# 40-auxiliary-octopus-cable.net
KiCad netlist of a schematic drawn in EAGLE
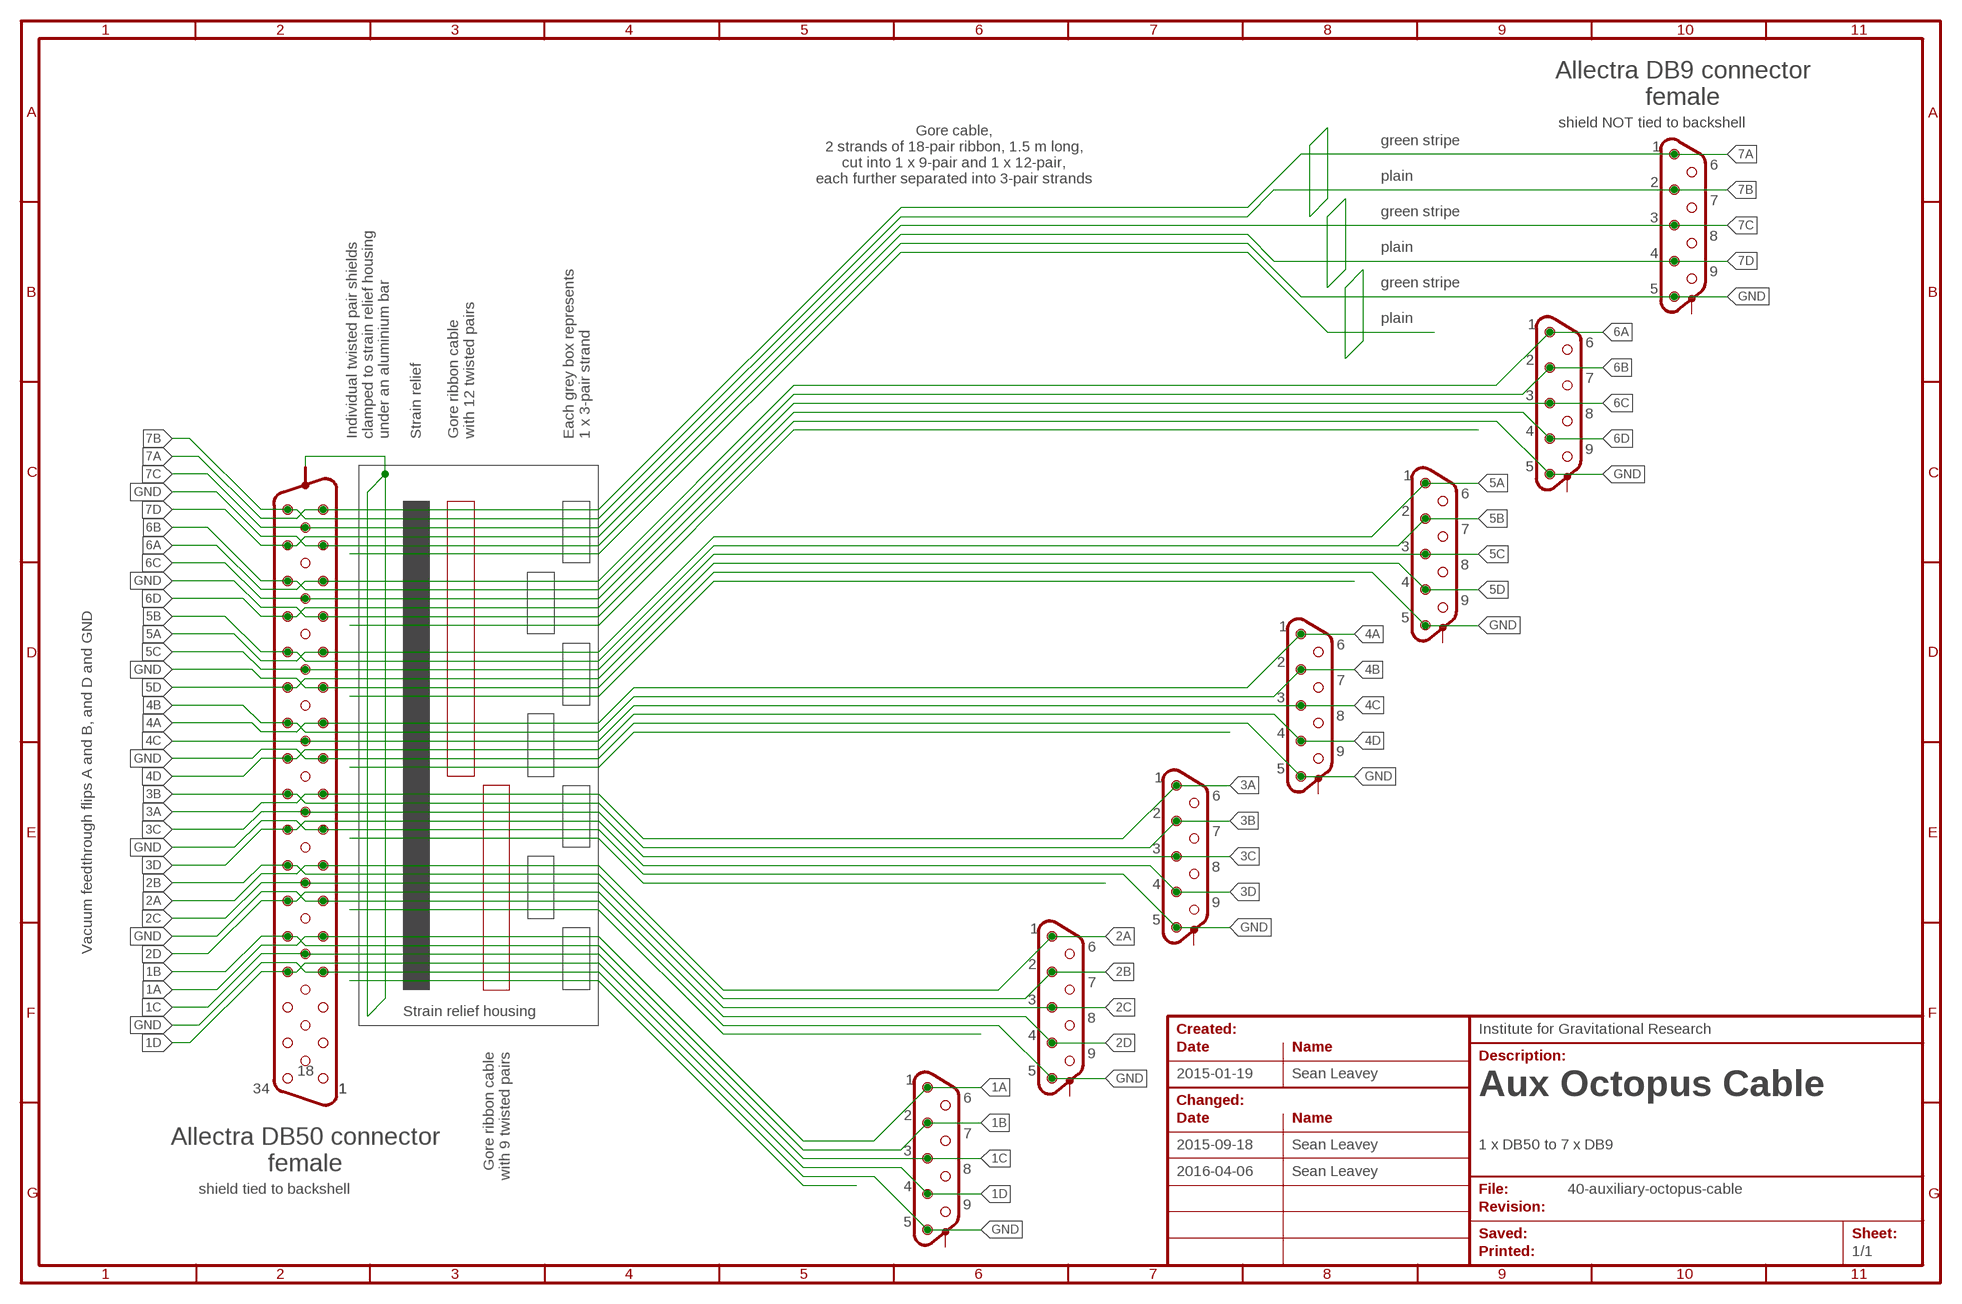
[diagram p0: schematic, sheet 1]

(export (version "E")
  (design (tool "Eeschema 10.0.6"))
  (components
    (comp (ref "U$7")
      (value "XDSUB50-SHIELD")
      (footprint "eagle-import:DUMMY50")
      (libsource (lib "eagle-import") (part "XDSUB50-SHIELD"))
    )
    (comp (ref "X43")
      (value "XDSUB9-SHIELD")
      (footprint "eagle-import:DUMMY10")
      (libsource (lib "eagle-import") (part "XDSUB9-SHIELD"))
    )
    (comp (ref "X44")
      (value "XDSUB9-SHIELD")
      (footprint "eagle-import:DUMMY10")
      (libsource (lib "eagle-import") (part "XDSUB9-SHIELD"))
    )
    (comp (ref "X45")
      (value "XDSUB9-SHIELD")
      (footprint "eagle-import:DUMMY10")
      (libsource (lib "eagle-import") (part "XDSUB9-SHIELD"))
    )
    (comp (ref "X46")
      (value "XDSUB9-SHIELD")
      (footprint "eagle-import:DUMMY10")
      (libsource (lib "eagle-import") (part "XDSUB9-SHIELD"))
    )
    (comp (ref "X47")
      (value "XDSUB9-SHIELD")
      (footprint "eagle-import:DUMMY10")
      (libsource (lib "eagle-import") (part "XDSUB9-SHIELD"))
    )
    (comp (ref "X53")
      (value "XDSUB9-SHIELD")
      (footprint "eagle-import:DUMMY10")
      (libsource (lib "eagle-import") (part "XDSUB9-SHIELD"))
    )
    (comp (ref "X54")
      (value "XDSUB9-SHIELD")
      (footprint "eagle-import:DUMMY10")
      (libsource (lib "eagle-import") (part "XDSUB9-SHIELD"))
    )
  )
  (nets
    (net (code "1") (name "1A") (class "Default")
      (node (ref "U$7") (pin "5") (pinfunction "5_5") (pintype "bidirectional"))
      (node (ref "X54") (pin "1") (pinfunction "1_1") (pintype "bidirectional"))
    )
    (net (code "2") (name "1B") (class "Default")
      (node (ref "U$7") (pin "38") (pinfunction "38_38") (pintype "bidirectional"))
      (node (ref "X54") (pin "2") (pinfunction "2_2") (pintype "bidirectional"))
    )
    (net (code "3") (name "1C") (class "Default")
      (node (ref "U$7") (pin "21") (pinfunction "21_21") (pintype "bidirectional"))
      (node (ref "X54") (pin "3") (pinfunction "3_3") (pintype "bidirectional"))
    )
    (net (code "4") (name "1D") (class "Default")
      (node (ref "U$7") (pin "37") (pinfunction "37_37") (pintype "bidirectional"))
      (node (ref "X54") (pin "4") (pinfunction "4_4") (pintype "bidirectional"))
    )
    (net (code "5") (name "2A") (class "Default")
      (node (ref "U$7") (pin "7") (pinfunction "7_7") (pintype "bidirectional"))
      (node (ref "X53") (pin "1") (pinfunction "1_1") (pintype "bidirectional"))
    )
    (net (code "6") (name "2B") (class "Default")
      (node (ref "U$7") (pin "40") (pinfunction "40_40") (pintype "bidirectional"))
      (node (ref "X53") (pin "2") (pinfunction "2_2") (pintype "bidirectional"))
    )
    (net (code "7") (name "2C") (class "Default")
      (node (ref "U$7") (pin "23") (pinfunction "23_23") (pintype "bidirectional"))
      (node (ref "X53") (pin "3") (pinfunction "3_3") (pintype "bidirectional"))
    )
    (net (code "8") (name "2D") (class "Default")
      (node (ref "U$7") (pin "39") (pinfunction "39_39") (pintype "bidirectional"))
      (node (ref "X53") (pin "4") (pinfunction "4_4") (pintype "bidirectional"))
    )
    (net (code "9") (name "3A") (class "Default")
      (node (ref "U$7") (pin "9") (pinfunction "9_9") (pintype "bidirectional"))
      (node (ref "X47") (pin "1") (pinfunction "1_1") (pintype "bidirectional"))
    )
    (net (code "10") (name "3B") (class "Default")
      (node (ref "U$7") (pin "42") (pinfunction "42_42") (pintype "bidirectional"))
      (node (ref "X47") (pin "2") (pinfunction "2_2") (pintype "bidirectional"))
    )
    (net (code "11") (name "3C") (class "Default")
      (node (ref "U$7") (pin "25") (pinfunction "25_25") (pintype "bidirectional"))
      (node (ref "X47") (pin "3") (pinfunction "3_3") (pintype "bidirectional"))
    )
    (net (code "12") (name "3D") (class "Default")
      (node (ref "U$7") (pin "41") (pinfunction "41_41") (pintype "bidirectional"))
      (node (ref "X47") (pin "4") (pinfunction "4_4") (pintype "bidirectional"))
    )
    (net (code "13") (name "4A") (class "Default")
      (node (ref "U$7") (pin "11") (pinfunction "11_11") (pintype "bidirectional"))
      (node (ref "X46") (pin "1") (pinfunction "1_1") (pintype "bidirectional"))
    )
    (net (code "14") (name "4B") (class "Default")
      (node (ref "U$7") (pin "44") (pinfunction "44_44") (pintype "bidirectional"))
      (node (ref "X46") (pin "2") (pinfunction "2_2") (pintype "bidirectional"))
    )
    (net (code "15") (name "4C") (class "Default")
      (node (ref "U$7") (pin "27") (pinfunction "27_27") (pintype "bidirectional"))
      (node (ref "X46") (pin "3") (pinfunction "3_3") (pintype "bidirectional"))
    )
    (net (code "16") (name "4D") (class "Default")
      (node (ref "U$7") (pin "43") (pinfunction "43_43") (pintype "bidirectional"))
      (node (ref "X46") (pin "4") (pinfunction "4_4") (pintype "bidirectional"))
    )
    (net (code "17") (name "5A") (class "Default")
      (node (ref "U$7") (pin "13") (pinfunction "13_13") (pintype "bidirectional"))
      (node (ref "X45") (pin "1") (pinfunction "1_1") (pintype "bidirectional"))
    )
    (net (code "18") (name "5B") (class "Default")
      (node (ref "U$7") (pin "46") (pinfunction "46_46") (pintype "bidirectional"))
      (node (ref "X45") (pin "2") (pinfunction "2_2") (pintype "bidirectional"))
    )
    (net (code "19") (name "5C") (class "Default")
      (node (ref "U$7") (pin "29") (pinfunction "29_29") (pintype "bidirectional"))
      (node (ref "X45") (pin "3") (pinfunction "3_3") (pintype "bidirectional"))
    )
    (net (code "20") (name "5D") (class "Default")
      (node (ref "U$7") (pin "45") (pinfunction "45_45") (pintype "bidirectional"))
      (node (ref "X45") (pin "4") (pinfunction "4_4") (pintype "bidirectional"))
    )
    (net (code "21") (name "6A") (class "Default")
      (node (ref "U$7") (pin "15") (pinfunction "15_15") (pintype "bidirectional"))
      (node (ref "X44") (pin "1") (pinfunction "1_1") (pintype "bidirectional"))
    )
    (net (code "22") (name "6B") (class "Default")
      (node (ref "U$7") (pin "48") (pinfunction "48_48") (pintype "bidirectional"))
      (node (ref "X44") (pin "2") (pinfunction "2_2") (pintype "bidirectional"))
    )
    (net (code "23") (name "6C") (class "Default")
      (node (ref "U$7") (pin "31") (pinfunction "31_31") (pintype "bidirectional"))
      (node (ref "X44") (pin "3") (pinfunction "3_3") (pintype "bidirectional"))
    )
    (net (code "24") (name "6D") (class "Default")
      (node (ref "U$7") (pin "47") (pinfunction "47_47") (pintype "bidirectional"))
      (node (ref "X44") (pin "4") (pinfunction "4_4") (pintype "bidirectional"))
    )
    (net (code "25") (name "7A") (class "Default")
      (node (ref "U$7") (pin "17") (pinfunction "17_17") (pintype "bidirectional"))
      (node (ref "X43") (pin "1") (pinfunction "1_1") (pintype "bidirectional"))
    )
    (net (code "26") (name "7B") (class "Default")
      (node (ref "U$7") (pin "50") (pinfunction "50_50") (pintype "bidirectional"))
      (node (ref "X43") (pin "2") (pinfunction "2_2") (pintype "bidirectional"))
    )
    (net (code "27") (name "7C") (class "Default")
      (node (ref "U$7") (pin "33") (pinfunction "33_33") (pintype "bidirectional"))
      (node (ref "X43") (pin "3") (pinfunction "3_3") (pintype "bidirectional"))
    )
    (net (code "28") (name "7D") (class "Default")
      (node (ref "U$7") (pin "49") (pinfunction "49_49") (pintype "bidirectional"))
      (node (ref "X43") (pin "4") (pinfunction "4_4") (pintype "bidirectional"))
    )
    (net (code "29") (name "GND") (class "Default")
      (node (ref "U$7") (pin "10") (pinfunction "10_10") (pintype "bidirectional"))
      (node (ref "U$7") (pin "12") (pinfunction "12_12") (pintype "bidirectional"))
      (node (ref "U$7") (pin "14") (pinfunction "14_14") (pintype "bidirectional"))
      (node (ref "U$7") (pin "16") (pinfunction "16_16") (pintype "bidirectional"))
      (node (ref "U$7") (pin "4") (pinfunction "4_4") (pintype "bidirectional"))
      (node (ref "U$7") (pin "6") (pinfunction "6_6") (pintype "bidirectional"))
      (node (ref "U$7") (pin "8") (pinfunction "8_8") (pintype "bidirectional"))
      (node (ref "X43") (pin "5") (pinfunction "5_5") (pintype "bidirectional"))
      (node (ref "X44") (pin "5") (pinfunction "5_5") (pintype "bidirectional"))
      (node (ref "X45") (pin "5") (pinfunction "5_5") (pintype "bidirectional"))
      (node (ref "X46") (pin "5") (pinfunction "5_5") (pintype "bidirectional"))
      (node (ref "X47") (pin "5") (pinfunction "5_5") (pintype "bidirectional"))
      (node (ref "X53") (pin "5") (pinfunction "5_5") (pintype "bidirectional"))
      (node (ref "X54") (pin "5") (pinfunction "5_5") (pintype "bidirectional"))
    )
    (net (code "30") (name "unconnected-(U$7-Pad1)") (class "Default")
      (node (ref "U$7") (pin "1") (pinfunction "1_1") (pintype "bidirectional"))
    )
    (net (code "31") (name "unconnected-(U$7-Pad2)") (class "Default")
      (node (ref "U$7") (pin "2") (pinfunction "2_2") (pintype "bidirectional"))
    )
    (net (code "32") (name "unconnected-(U$7-Pad3)") (class "Default")
      (node (ref "U$7") (pin "3") (pinfunction "3_3") (pintype "bidirectional"))
    )
    (net (code "33") (name "unconnected-(U$7-Pad18)") (class "Default")
      (node (ref "U$7") (pin "18") (pinfunction "18_18") (pintype "bidirectional"))
    )
    (net (code "34") (name "unconnected-(U$7-Pad19)") (class "Default")
      (node (ref "U$7") (pin "19") (pinfunction "19_19") (pintype "bidirectional"))
    )
    (net (code "35") (name "unconnected-(U$7-Pad20)") (class "Default")
      (node (ref "U$7") (pin "20") (pinfunction "20_20") (pintype "bidirectional"))
    )
    (net (code "36") (name "unconnected-(U$7-Pad22)") (class "Default")
      (node (ref "U$7") (pin "22") (pinfunction "22_22") (pintype "bidirectional"))
    )
    (net (code "37") (name "unconnected-(U$7-Pad24)") (class "Default")
      (node (ref "U$7") (pin "24") (pinfunction "24_24") (pintype "bidirectional"))
    )
    (net (code "38") (name "unconnected-(U$7-Pad26)") (class "Default")
      (node (ref "U$7") (pin "26") (pinfunction "26_26") (pintype "bidirectional"))
    )
    (net (code "39") (name "unconnected-(U$7-Pad28)") (class "Default")
      (node (ref "U$7") (pin "28") (pinfunction "28_28") (pintype "bidirectional"))
    )
    (net (code "40") (name "unconnected-(U$7-Pad30)") (class "Default")
      (node (ref "U$7") (pin "30") (pinfunction "30_30") (pintype "bidirectional"))
    )
    (net (code "41") (name "unconnected-(U$7-Pad32)") (class "Default")
      (node (ref "U$7") (pin "32") (pinfunction "32_32") (pintype "bidirectional"))
    )
    (net (code "42") (name "unconnected-(U$7-Pad34)") (class "Default")
      (node (ref "U$7") (pin "34") (pinfunction "34_34") (pintype "bidirectional"))
    )
    (net (code "43") (name "unconnected-(U$7-Pad35)") (class "Default")
      (node (ref "U$7") (pin "35") (pinfunction "35_35") (pintype "bidirectional"))
    )
    (net (code "44") (name "unconnected-(U$7-Pad36)") (class "Default")
      (node (ref "U$7") (pin "36") (pinfunction "36_36") (pintype "bidirectional"))
    )
    (net (code "45") (name "unconnected-(U$7-S-Pad51)") (class "Default")
      (node (ref "U$7") (pin "51") (pinfunction "S_51") (pintype "bidirectional"))
    )
    (net (code "46") (name "unconnected-(X43-Pad6)") (class "Default")
      (node (ref "X43") (pin "6") (pinfunction "6_6") (pintype "bidirectional"))
    )
    (net (code "47") (name "unconnected-(X43-Pad7)") (class "Default")
      (node (ref "X43") (pin "7") (pinfunction "7_7") (pintype "bidirectional"))
    )
    (net (code "48") (name "unconnected-(X43-Pad8)") (class "Default")
      (node (ref "X43") (pin "8") (pinfunction "8_8") (pintype "bidirectional"))
    )
    (net (code "49") (name "unconnected-(X43-Pad9)") (class "Default")
      (node (ref "X43") (pin "9") (pinfunction "9_9") (pintype "bidirectional"))
    )
    (net (code "50") (name "unconnected-(X43-S-Pad10)") (class "Default")
      (node (ref "X43") (pin "10") (pinfunction "S_10") (pintype "bidirectional"))
    )
    (net (code "51") (name "unconnected-(X44-Pad6)") (class "Default")
      (node (ref "X44") (pin "6") (pinfunction "6_6") (pintype "bidirectional"))
    )
    (net (code "52") (name "unconnected-(X44-Pad7)") (class "Default")
      (node (ref "X44") (pin "7") (pinfunction "7_7") (pintype "bidirectional"))
    )
    (net (code "53") (name "unconnected-(X44-Pad8)") (class "Default")
      (node (ref "X44") (pin "8") (pinfunction "8_8") (pintype "bidirectional"))
    )
    (net (code "54") (name "unconnected-(X44-Pad9)") (class "Default")
      (node (ref "X44") (pin "9") (pinfunction "9_9") (pintype "bidirectional"))
    )
    (net (code "55") (name "unconnected-(X44-S-Pad10)") (class "Default")
      (node (ref "X44") (pin "10") (pinfunction "S_10") (pintype "bidirectional"))
    )
    (net (code "56") (name "unconnected-(X45-Pad6)") (class "Default")
      (node (ref "X45") (pin "6") (pinfunction "6_6") (pintype "bidirectional"))
    )
    (net (code "57") (name "unconnected-(X45-Pad7)") (class "Default")
      (node (ref "X45") (pin "7") (pinfunction "7_7") (pintype "bidirectional"))
    )
    (net (code "58") (name "unconnected-(X45-Pad8)") (class "Default")
      (node (ref "X45") (pin "8") (pinfunction "8_8") (pintype "bidirectional"))
    )
    (net (code "59") (name "unconnected-(X45-Pad9)") (class "Default")
      (node (ref "X45") (pin "9") (pinfunction "9_9") (pintype "bidirectional"))
    )
    (net (code "60") (name "unconnected-(X45-S-Pad10)") (class "Default")
      (node (ref "X45") (pin "10") (pinfunction "S_10") (pintype "bidirectional"))
    )
    (net (code "61") (name "unconnected-(X46-Pad6)") (class "Default")
      (node (ref "X46") (pin "6") (pinfunction "6_6") (pintype "bidirectional"))
    )
    (net (code "62") (name "unconnected-(X46-Pad7)") (class "Default")
      (node (ref "X46") (pin "7") (pinfunction "7_7") (pintype "bidirectional"))
    )
    (net (code "63") (name "unconnected-(X46-Pad8)") (class "Default")
      (node (ref "X46") (pin "8") (pinfunction "8_8") (pintype "bidirectional"))
    )
    (net (code "64") (name "unconnected-(X46-Pad9)") (class "Default")
      (node (ref "X46") (pin "9") (pinfunction "9_9") (pintype "bidirectional"))
    )
    (net (code "65") (name "unconnected-(X46-S-Pad10)") (class "Default")
      (node (ref "X46") (pin "10") (pinfunction "S_10") (pintype "bidirectional"))
    )
    (net (code "66") (name "unconnected-(X47-Pad6)") (class "Default")
      (node (ref "X47") (pin "6") (pinfunction "6_6") (pintype "bidirectional"))
    )
    (net (code "67") (name "unconnected-(X47-Pad7)") (class "Default")
      (node (ref "X47") (pin "7") (pinfunction "7_7") (pintype "bidirectional"))
    )
    (net (code "68") (name "unconnected-(X47-Pad8)") (class "Default")
      (node (ref "X47") (pin "8") (pinfunction "8_8") (pintype "bidirectional"))
    )
    (net (code "69") (name "unconnected-(X47-Pad9)") (class "Default")
      (node (ref "X47") (pin "9") (pinfunction "9_9") (pintype "bidirectional"))
    )
    (net (code "70") (name "unconnected-(X47-S-Pad10)") (class "Default")
      (node (ref "X47") (pin "10") (pinfunction "S_10") (pintype "bidirectional"))
    )
    (net (code "71") (name "unconnected-(X53-Pad6)") (class "Default")
      (node (ref "X53") (pin "6") (pinfunction "6_6") (pintype "bidirectional"))
    )
    (net (code "72") (name "unconnected-(X53-Pad7)") (class "Default")
      (node (ref "X53") (pin "7") (pinfunction "7_7") (pintype "bidirectional"))
    )
    (net (code "73") (name "unconnected-(X53-Pad8)") (class "Default")
      (node (ref "X53") (pin "8") (pinfunction "8_8") (pintype "bidirectional"))
    )
    (net (code "74") (name "unconnected-(X53-Pad9)") (class "Default")
      (node (ref "X53") (pin "9") (pinfunction "9_9") (pintype "bidirectional"))
    )
    (net (code "75") (name "unconnected-(X53-S-Pad10)") (class "Default")
      (node (ref "X53") (pin "10") (pinfunction "S_10") (pintype "bidirectional"))
    )
    (net (code "76") (name "unconnected-(X54-Pad6)") (class "Default")
      (node (ref "X54") (pin "6") (pinfunction "6_6") (pintype "bidirectional"))
    )
    (net (code "77") (name "unconnected-(X54-Pad7)") (class "Default")
      (node (ref "X54") (pin "7") (pinfunction "7_7") (pintype "bidirectional"))
    )
    (net (code "78") (name "unconnected-(X54-Pad8)") (class "Default")
      (node (ref "X54") (pin "8") (pinfunction "8_8") (pintype "bidirectional"))
    )
    (net (code "79") (name "unconnected-(X54-Pad9)") (class "Default")
      (node (ref "X54") (pin "9") (pinfunction "9_9") (pintype "bidirectional"))
    )
    (net (code "80") (name "unconnected-(X54-S-Pad10)") (class "Default")
      (node (ref "X54") (pin "10") (pinfunction "S_10") (pintype "bidirectional"))
    )
  )
)
